# solar_tracker.net
KiCad netlist of a schematic drawn in EAGLE
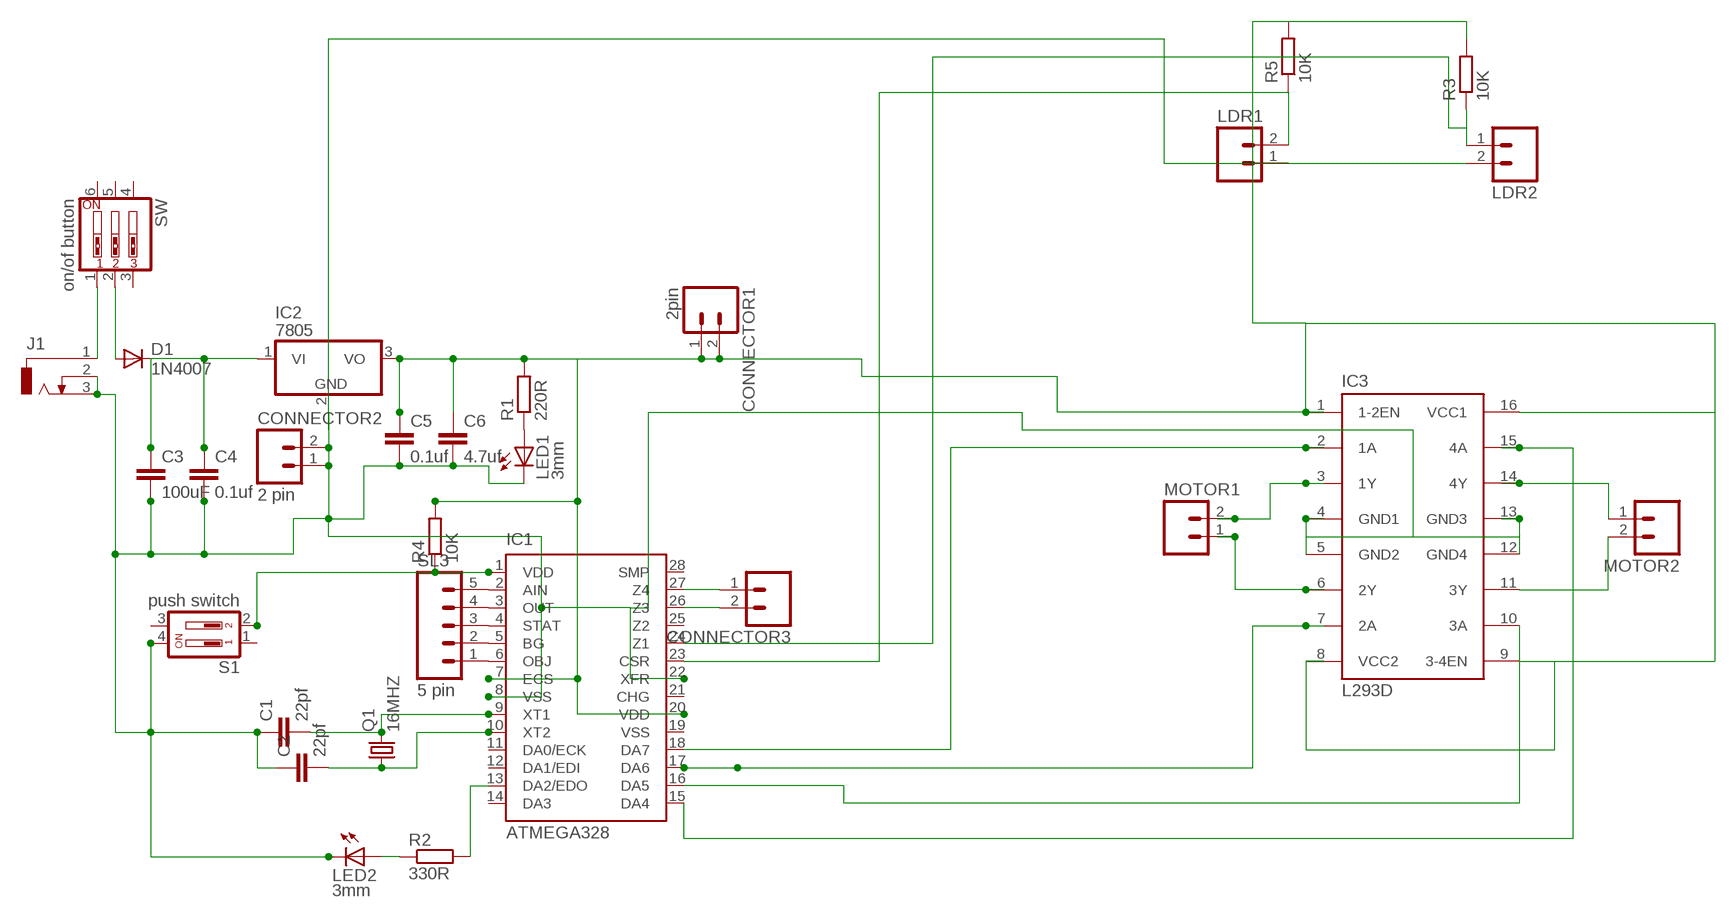
[diagram p0: schematic, sheet 1]

(export (version "E")
  (design (tool "Eeschema 10.0.6"))
  (components
    (comp (ref "C1")
      (value "22pf")
      (footprint "eagle-import:C2.5-2")
      (libsource (lib "eagle-import") (part "C2.5/2"))
    )
    (comp (ref "C2")
      (value "22pf")
      (footprint "eagle-import:C2.5-2")
      (libsource (lib "eagle-import") (part "C2.5/2"))
    )
    (comp (ref "C3")
      (value "100uF")
      (footprint "eagle-import:C2.5-2")
      (libsource (lib "eagle-import") (part "C2.5/2"))
    )
    (comp (ref "C4")
      (value "0.1uf")
      (footprint "eagle-import:C2.5-2")
      (libsource (lib "eagle-import") (part "C2.5/2"))
    )
    (comp (ref "C5")
      (value "0.1uf")
      (footprint "eagle-import:C2.5-2")
      (libsource (lib "eagle-import") (part "C2.5/2"))
    )
    (comp (ref "C6")
      (value "4.7uf")
      (footprint "eagle-import:C2.5-2")
      (libsource (lib "eagle-import") (part "C2.5/2"))
    )
    (comp (ref "CONNECTOR1")
      (value "2pin")
      (footprint "eagle-import:02P")
      (fields (field (name "OC_FARNELL") "unknown") (field (name "OC_NEWARK") "unknown"))
      (libsource (lib "eagle-import") (part "M02"))
    )
    (comp (ref "CONNECTOR2")
      (value "2 pin")
      (footprint "eagle-import:02P")
      (fields (field (name "OC_FARNELL") "unknown") (field (name "OC_NEWARK") "unknown"))
      (libsource (lib "eagle-import") (part "M02"))
    )
    (comp (ref "CONNECTOR3")
      (value "M02")
      (footprint "eagle-import:02P")
      (fields (field (name "OC_FARNELL") "unknown") (field (name "OC_NEWARK") "unknown"))
      (libsource (lib "eagle-import") (part "M02"))
    )
    (comp (ref "D1")
      (value "1N4007")
      (footprint "eagle-import:DO41-10")
      (libsource (lib "eagle-import") (part "1N4004"))
    )
    (comp (ref "IC1")
      (value "ATMEGA328")
      (footprint "eagle-import:DIL28-3")
      (libsource (lib "eagle-import") (part "QT9701BD"))
    )
    (comp (ref "IC2")
      (value "7805")
      (footprint "eagle-import:TO220V")
      (libsource (lib "eagle-import") (part "78TV6"))
    )
    (comp (ref "IC3")
      (value "L293D")
      (footprint "eagle-import:DIL16")
      (libsource (lib "eagle-import") (part "L293D"))
    )
    (comp (ref "J1")
      (value "DCJ0303")
      (footprint "eagle-import:DCJ0303")
      (libsource (lib "eagle-import") (part "DCJ0303"))
    )
    (comp (ref "LDR1")
      (value "M02")
      (footprint "eagle-import:02P")
      (fields (field (name "OC_FARNELL") "unknown") (field (name "OC_NEWARK") "unknown"))
      (libsource (lib "eagle-import") (part "M02"))
    )
    (comp (ref "LDR2")
      (value "M02")
      (footprint "eagle-import:02P")
      (fields (field (name "OC_FARNELL") "unknown") (field (name "OC_NEWARK") "unknown"))
      (libsource (lib "eagle-import") (part "M02"))
    )
    (comp (ref "LED1")
      (value "3mm")
      (footprint "eagle-import:LED3MM")
      (libsource (lib "eagle-import") (part "LED3MM"))
    )
    (comp (ref "LED2")
      (value "3mm")
      (footprint "eagle-import:LED3MM")
      (libsource (lib "eagle-import") (part "LED3MM"))
    )
    (comp (ref "MOTOR1")
      (value "M02")
      (footprint "eagle-import:02P")
      (fields (field (name "OC_FARNELL") "unknown") (field (name "OC_NEWARK") "unknown"))
      (libsource (lib "eagle-import") (part "M02"))
    )
    (comp (ref "MOTOR2")
      (value "M02")
      (footprint "eagle-import:02P")
      (libsource (lib "eagle-import") (part "M02"))
    )
    (comp (ref "Q1")
      (value "16MHZ")
      (footprint "eagle-import:HC49_S")
      (libsource (lib "eagle-import") (part "CRYSTALHC49S"))
    )
    (comp (ref "R1")
      (value "220R")
      (footprint "eagle-import:0207_10")
      (libsource (lib "eagle-import") (part "R-EU_0207/10"))
    )
    (comp (ref "R2")
      (value "330R")
      (footprint "eagle-import:0207_10")
      (libsource (lib "eagle-import") (part "R-EU_0207/10"))
    )
    (comp (ref "R3")
      (value "10K")
      (footprint "eagle-import:0207_10")
      (libsource (lib "eagle-import") (part "R-EU_0207/10"))
    )
    (comp (ref "R4")
      (value "10K")
      (footprint "eagle-import:0207_10")
      (libsource (lib "eagle-import") (part "R-EU_0207/10"))
    )
    (comp (ref "R5")
      (value "10K")
      (footprint "eagle-import:0207_10")
      (libsource (lib "eagle-import") (part "R-EU_0207/10"))
    )
    (comp (ref "S1")
      (value "push switch")
      (footprint "eagle-import:DP-02")
      (fields (field (name "MPN") "MCDP02"))
      (libsource (lib "eagle-import") (part "DP02"))
    )
    (comp (ref "SL3")
      (value "5 pin")
      (footprint "eagle-import:05P")
      (libsource (lib "eagle-import") (part "M05"))
    )
    (comp (ref "SW")
      (value "on/of button")
      (footprint "eagle-import:EDG-03")
      (libsource (lib "eagle-import") (part "SW_DIP-3"))
    )
  )
  (nets
    (net (code "1") (name "Net-(D1-PadA)") (class "Default")
      (node (ref "D1") (pin "A") (pinfunction "A_A") (pintype "passive"))
      (node (ref "SW") (pin "2") (pinfunction "2_2") (pintype "passive"))
    )
    (net (code "2") (name "Net-(IC1-AIN)") (class "Default")
      (node (ref "IC1") (pin "2") (pinfunction "AIN_2") (pintype "input"))
      (node (ref "SL3") (pin "5") (pinfunction "5_5") (pintype "passive"))
    )
    (net (code "3") (name "Net-(IC1-BG)") (class "Default")
      (node (ref "IC1") (pin "5") (pinfunction "BG_5") (pintype "input"))
      (node (ref "SL3") (pin "2") (pinfunction "2_2") (pintype "passive"))
    )
    (net (code "4") (name "Net-(IC1-CSR)") (class "Default")
      (node (ref "IC1") (pin "23") (pinfunction "CSR_23") (pintype "output"))
      (node (ref "LDR1") (pin "2") (pinfunction "2_2") (pintype "passive"))
      (node (ref "R5") (pin "1") (pinfunction "1_1") (pintype "passive"))
    )
    (net (code "5") (name "Net-(IC1-DA2{slash}EDO)") (class "Default")
      (node (ref "IC1") (pin "13") (pinfunction "DA2/EDO_13") (pintype "output"))
      (node (ref "R2") (pin "2") (pinfunction "2_2") (pintype "passive"))
    )
    (net (code "6") (name "Net-(IC1-DA4)") (class "Default")
      (node (ref "IC1") (pin "15") (pinfunction "DA4_15") (pintype "output"))
      (node (ref "IC3") (pin "15") (pinfunction "4A_15") (pintype "input"))
    )
    (net (code "7") (name "Net-(IC1-DA5)") (class "Default")
      (node (ref "IC1") (pin "16") (pinfunction "DA5_16") (pintype "output"))
      (node (ref "IC3") (pin "10") (pinfunction "3A_10") (pintype "input"))
    )
    (net (code "8") (name "Net-(IC1-DA6)") (class "Default")
      (node (ref "IC1") (pin "17") (pinfunction "DA6_17") (pintype "output"))
      (node (ref "IC3") (pin "7") (pinfunction "2A_7") (pintype "input"))
    )
    (net (code "9") (name "Net-(IC1-DA7)") (class "Default")
      (node (ref "IC1") (pin "18") (pinfunction "DA7_18") (pintype "output"))
      (node (ref "IC3") (pin "2") (pinfunction "1A_2") (pintype "input"))
    )
    (net (code "10") (name "Net-(IC1-ECS)") (class "Default")
      (node (ref "C5") (pin "1") (pinfunction "1_1") (pintype "passive"))
      (node (ref "C6") (pin "1") (pinfunction "1_1") (pintype "passive"))
      (node (ref "CONNECTOR1") (pin "1") (pinfunction "1_1") (pintype "passive"))
      (node (ref "CONNECTOR1") (pin "2") (pinfunction "2_2") (pintype "passive"))
      (node (ref "IC1") (pin "20") (pinfunction "VDD_20") (pintype "input"))
      (node (ref "IC1") (pin "7") (pinfunction "ECS_7") (pintype "output"))
      (node (ref "IC2") (pin "3") (pinfunction "VO_3") (pintype "passive"))
      (node (ref "IC3") (pin "1") (pinfunction "1-2EN_1") (pintype "input"))
      (node (ref "IC3") (pin "16") (pinfunction "VCC1_16") (pintype "power_in"))
      (node (ref "IC3") (pin "8") (pinfunction "VCC2_8") (pintype "power_in"))
      (node (ref "IC3") (pin "9") (pinfunction "3-4EN_9") (pintype "input"))
      (node (ref "R1") (pin "2") (pinfunction "2_2") (pintype "passive"))
      (node (ref "R3") (pin "2") (pinfunction "2_2") (pintype "passive"))
      (node (ref "R4") (pin "2") (pinfunction "2_2") (pintype "passive"))
      (node (ref "R5") (pin "2") (pinfunction "2_2") (pintype "passive"))
    )
    (net (code "11") (name "Net-(IC1-OBJ)") (class "Default")
      (node (ref "IC1") (pin "6") (pinfunction "OBJ_6") (pintype "input"))
      (node (ref "SL3") (pin "1") (pinfunction "1_1") (pintype "passive"))
    )
    (net (code "12") (name "Net-(IC1-OUT)") (class "Default")
      (node (ref "IC1") (pin "3") (pinfunction "OUT_3") (pintype "output"))
      (node (ref "SL3") (pin "4") (pinfunction "4_4") (pintype "passive"))
    )
    (net (code "13") (name "Net-(IC1-STAT)") (class "Default")
      (node (ref "IC1") (pin "4") (pinfunction "STAT_4") (pintype "output"))
      (node (ref "SL3") (pin "3") (pinfunction "3_3") (pintype "passive"))
    )
    (net (code "14") (name "Net-(IC1-VDD-Pad1)") (class "Default")
      (node (ref "IC1") (pin "1") (pinfunction "VDD_1") (pintype "input"))
      (node (ref "R4") (pin "1") (pinfunction "1_1") (pintype "passive"))
      (node (ref "S1") (pin "2") (pinfunction "2_2") (pintype "passive"))
    )
    (net (code "15") (name "Net-(IC1-XFR)") (class "Default")
      (node (ref "C1") (pin "1") (pinfunction "1_1") (pintype "passive"))
      (node (ref "C2") (pin "1") (pinfunction "1_1") (pintype "passive"))
      (node (ref "C3") (pin "2") (pinfunction "2_2") (pintype "passive"))
      (node (ref "C4") (pin "2") (pinfunction "2_2") (pintype "passive"))
      (node (ref "C5") (pin "2") (pinfunction "2_2") (pintype "passive"))
      (node (ref "C6") (pin "2") (pinfunction "2_2") (pintype "passive"))
      (node (ref "CONNECTOR2") (pin "1") (pinfunction "1_1") (pintype "passive"))
      (node (ref "CONNECTOR2") (pin "2") (pinfunction "2_2") (pintype "passive"))
      (node (ref "IC1") (pin "22") (pinfunction "XFR_22") (pintype "output"))
      (node (ref "IC1") (pin "8") (pinfunction "VSS_8") (pintype "input"))
      (node (ref "IC2") (pin "2") (pinfunction "GND_2") (pintype "passive"))
      (node (ref "IC3") (pin "12") (pinfunction "GND4_12") (pintype "power_in"))
      (node (ref "IC3") (pin "13") (pinfunction "GND3_13") (pintype "power_in"))
      (node (ref "IC3") (pin "4") (pinfunction "GND1_4") (pintype "power_in"))
      (node (ref "IC3") (pin "5") (pinfunction "GND2_5") (pintype "power_in"))
      (node (ref "J1") (pin "2") (pinfunction "2_2") (pintype "passive"))
      (node (ref "J1") (pin "3") (pinfunction "3_3") (pintype "passive"))
      (node (ref "LDR1") (pin "1") (pinfunction "1_1") (pintype "passive"))
      (node (ref "LDR2") (pin "2") (pinfunction "2_2") (pintype "passive"))
      (node (ref "LED1") (pin "K") (pinfunction "C_K") (pintype "passive"))
      (node (ref "LED2") (pin "K") (pinfunction "C_K") (pintype "passive"))
      (node (ref "S1") (pin "4") (pinfunction "4_4") (pintype "passive"))
    )
    (net (code "16") (name "Net-(IC1-XT1)") (class "Default")
      (node (ref "C1") (pin "2") (pinfunction "2_2") (pintype "passive"))
      (node (ref "IC1") (pin "9") (pinfunction "XT1_9") (pintype "input"))
      (node (ref "Q1") (pin "2") (pinfunction "2_2") (pintype "passive"))
    )
    (net (code "17") (name "Net-(IC1-XT2)") (class "Default")
      (node (ref "C2") (pin "2") (pinfunction "2_2") (pintype "passive"))
      (node (ref "IC1") (pin "10") (pinfunction "XT2_10") (pintype "output"))
      (node (ref "Q1") (pin "1") (pinfunction "1_1") (pintype "passive"))
    )
    (net (code "18") (name "Net-(IC1-Z1)") (class "Default")
      (node (ref "IC1") (pin "24") (pinfunction "Z1_24") (pintype "output"))
      (node (ref "LDR2") (pin "1") (pinfunction "1_1") (pintype "passive"))
      (node (ref "R3") (pin "1") (pinfunction "1_1") (pintype "passive"))
    )
    (net (code "19") (name "Net-(IC1-Z3)") (class "Default")
      (node (ref "CONNECTOR3") (pin "2") (pinfunction "2_2") (pintype "passive"))
      (node (ref "IC1") (pin "26") (pinfunction "Z3_26") (pintype "output"))
    )
    (net (code "20") (name "Net-(IC1-Z4)") (class "Default")
      (node (ref "CONNECTOR3") (pin "1") (pinfunction "1_1") (pintype "passive"))
      (node (ref "IC1") (pin "27") (pinfunction "Z4_27") (pintype "output"))
    )
    (net (code "21") (name "Net-(IC2-VI)") (class "Default")
      (node (ref "C3") (pin "1") (pinfunction "1_1") (pintype "passive"))
      (node (ref "C4") (pin "1") (pinfunction "1_1") (pintype "passive"))
      (node (ref "D1") (pin "C") (pinfunction "C_C") (pintype "passive"))
      (node (ref "IC2") (pin "1") (pinfunction "VI_1") (pintype "input"))
    )
    (net (code "22") (name "Net-(IC3-1Y)") (class "Default")
      (node (ref "IC3") (pin "3") (pinfunction "1Y_3") (pintype "output"))
      (node (ref "MOTOR1") (pin "2") (pinfunction "2_2") (pintype "passive"))
    )
    (net (code "23") (name "Net-(IC3-2Y)") (class "Default")
      (node (ref "IC3") (pin "6") (pinfunction "2Y_6") (pintype "output"))
      (node (ref "MOTOR1") (pin "1") (pinfunction "1_1") (pintype "passive"))
    )
    (net (code "24") (name "Net-(IC3-3Y)") (class "Default")
      (node (ref "IC3") (pin "11") (pinfunction "3Y_11") (pintype "output"))
      (node (ref "MOTOR2") (pin "2") (pinfunction "2_2") (pintype "passive"))
    )
    (net (code "25") (name "Net-(IC3-4Y)") (class "Default")
      (node (ref "IC3") (pin "14") (pinfunction "4Y_14") (pintype "output"))
      (node (ref "MOTOR2") (pin "1") (pinfunction "1_1") (pintype "passive"))
    )
    (net (code "26") (name "Net-(J1-Pad1)") (class "Default")
      (node (ref "J1") (pin "1") (pinfunction "1_1") (pintype "passive"))
      (node (ref "SW") (pin "1") (pinfunction "1_1") (pintype "passive"))
    )
    (net (code "27") (name "Net-(LED1-PadA)") (class "Default")
      (node (ref "LED1") (pin "A") (pinfunction "A_A") (pintype "passive"))
      (node (ref "R1") (pin "1") (pinfunction "1_1") (pintype "passive"))
    )
    (net (code "28") (name "Net-(LED2-PadA)") (class "Default")
      (node (ref "LED2") (pin "A") (pinfunction "A_A") (pintype "passive"))
      (node (ref "R2") (pin "1") (pinfunction "1_1") (pintype "passive"))
    )
    (net (code "29") (name "unconnected-(IC1-CHG-Pad21)") (class "Default")
      (node (ref "IC1") (pin "21") (pinfunction "CHG_21") (pintype "output"))
    )
    (net (code "30") (name "unconnected-(IC1-DA0{slash}ECK-Pad11)") (class "Default")
      (node (ref "IC1") (pin "11") (pinfunction "DA0/ECK_11") (pintype "output"))
    )
    (net (code "31") (name "unconnected-(IC1-DA1{slash}EDI-Pad12)") (class "Default")
      (node (ref "IC1") (pin "12") (pinfunction "DA1/EDI_12") (pintype "output"))
    )
    (net (code "32") (name "unconnected-(IC1-DA3-Pad14)") (class "Default")
      (node (ref "IC1") (pin "14") (pinfunction "DA3_14") (pintype "output"))
    )
    (net (code "33") (name "unconnected-(IC1-SMP-Pad28)") (class "Default")
      (node (ref "IC1") (pin "28") (pinfunction "SMP_28") (pintype "output"))
    )
    (net (code "34") (name "unconnected-(IC1-VSS-Pad19)") (class "Default")
      (node (ref "IC1") (pin "19") (pinfunction "VSS_19") (pintype "input"))
    )
    (net (code "35") (name "unconnected-(IC1-Z2-Pad25)") (class "Default")
      (node (ref "IC1") (pin "25") (pinfunction "Z2_25") (pintype "output"))
    )
    (net (code "36") (name "unconnected-(S1-Pad1)") (class "Default")
      (node (ref "S1") (pin "1") (pinfunction "1_1") (pintype "passive"))
    )
    (net (code "37") (name "unconnected-(S1-Pad3)") (class "Default")
      (node (ref "S1") (pin "3") (pinfunction "3_3") (pintype "passive"))
    )
    (net (code "38") (name "unconnected-(SW-Pad3)") (class "Default")
      (node (ref "SW") (pin "3") (pinfunction "3_3") (pintype "passive"))
    )
    (net (code "39") (name "unconnected-(SW-Pad4)") (class "Default")
      (node (ref "SW") (pin "4") (pinfunction "4_4") (pintype "passive"))
    )
    (net (code "40") (name "unconnected-(SW-Pad5)") (class "Default")
      (node (ref "SW") (pin "5") (pinfunction "5_5") (pintype "passive"))
    )
    (net (code "41") (name "unconnected-(SW-Pad6)") (class "Default")
      (node (ref "SW") (pin "6") (pinfunction "6_6") (pintype "passive"))
    )
  )
)
